# Voltage_Source.net
KiCad netlist of a schematic drawn in Altium Designer
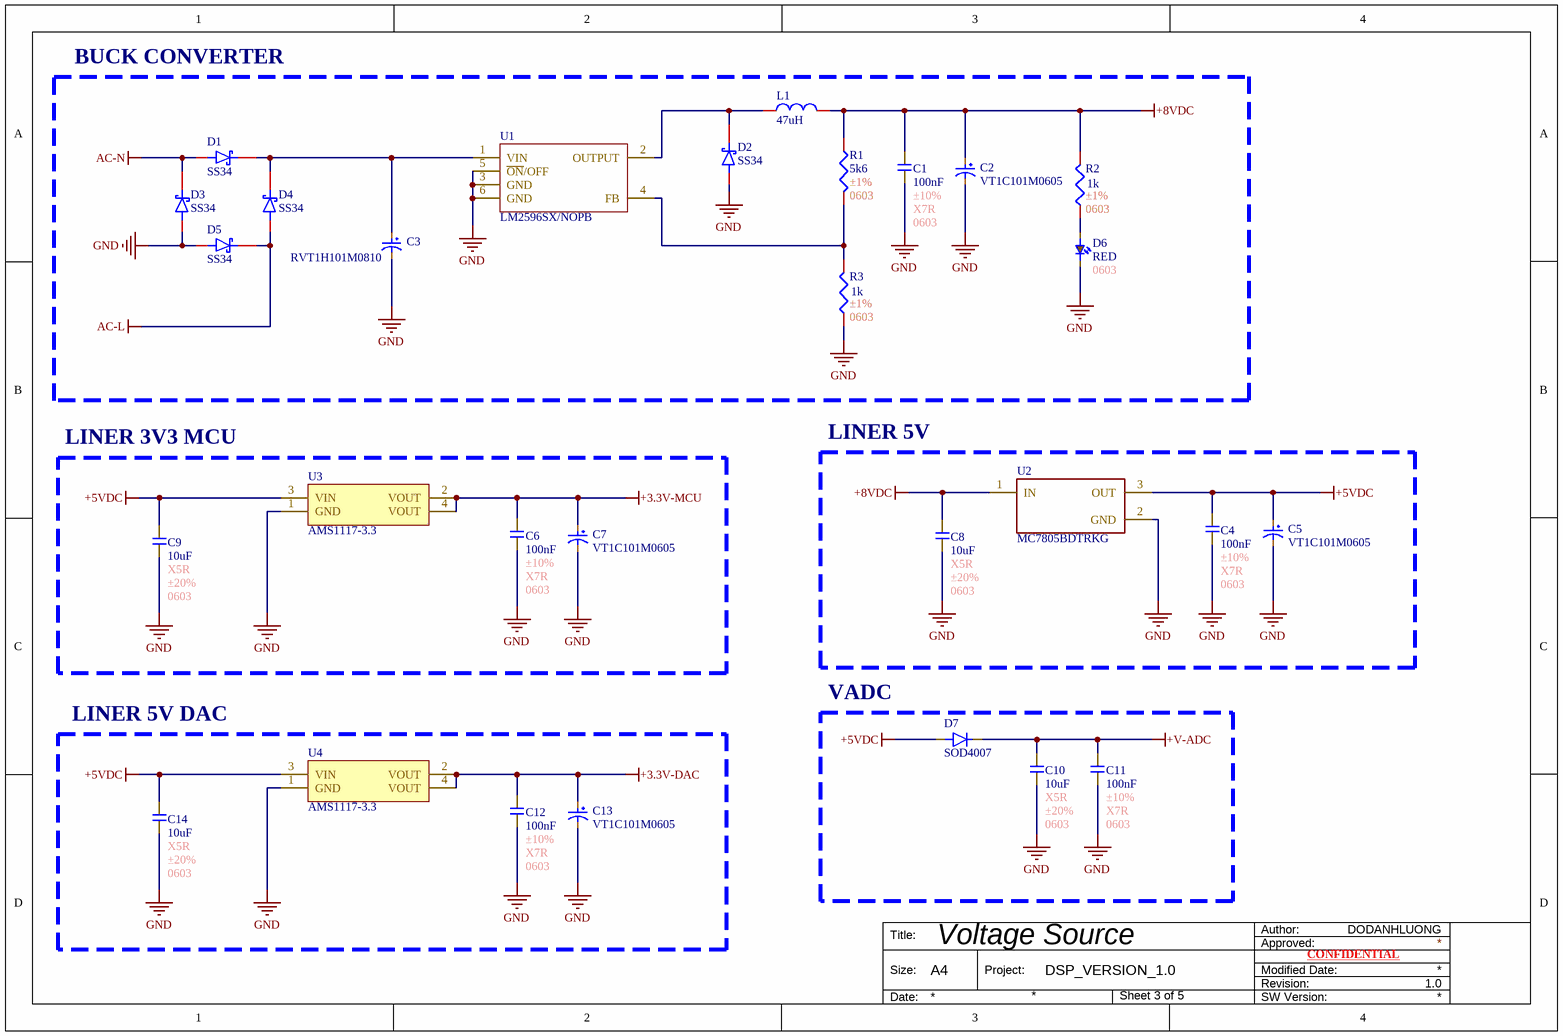
[diagram p0: Voltage Source.SchDoc]

(export (version "E")
  (design (tool "Eeschema 10.0.6"))
  (components
    (comp (ref "C1")
      (value "100nF")
      (footprint "C0603")
      (description "50V 100nF X7R ±10% 0603 Multilayer Ceramic Capacitors MLCC - SMD/SMT ROHS")
      (fields
        (field (name "MANUFACTURER") "YAGEO")
        (field (name "MFR. PART #") "CC0603KRX7R9BB104")
        (field (name "TOLERANCE") "±10%")
        (field (name "TEMPERATURE COEFFICIENT") "X7R")
        (field (name "PACKAGE") "0603")
      )
      (libsource (lib "DSP_VERSION_1.0") (part "C0603_100nF_±10%_X7R"))
    )
    (comp (ref "C2")
      (value "VT1C101M0605")
      (footprint "C_100uF_16V_Aluminum")
      (description "100uF 16V ±20% 63mA@120Hz SMD,D6.3xL5.4mm Aluminum Electrolytic Capacitors RoHS")
      (fields (field (name "MANUFACTURER") "ROQANG") (field (name "LCSC PART #") "C90273"))
      (libsource (lib "Capital") (part "C_100uF_16V_aluminum"))
    )
    (comp (ref "C3")
      (value "RVT1H101M0810")
      (footprint "C_100uF_Aluminum")
      (description "100uF 50V ±20% 146mA@120Hz SMD,D8xL10.2mm Aluminum Electrolytic Capacitors RoHS")
      (fields (field (name "MANUFACTURER") "ROQANG") (field (name "LCSC PART #") "C72480"))
      (libsource (lib "Capital") (part "C_100uF_aluminum"))
    )
    (comp (ref "C4")
      (value "100nF")
      (footprint "C0603")
      (description "50V 100nF X7R ±10% 0603 Multilayer Ceramic Capacitors MLCC - SMD/SMT ROHS")
      (fields
        (field (name "MANUFACTURER") "YAGEO")
        (field (name "MFR. PART #") "CC0603KRX7R9BB104")
        (field (name "TOLERANCE") "±10%")
        (field (name "TEMPERATURE COEFFICIENT") "X7R")
        (field (name "PACKAGE") "0603")
      )
      (libsource (lib "DSP_VERSION_1.0") (part "C0603_100nF_±10%_X7R"))
    )
    (comp (ref "C5")
      (value "VT1C101M0605")
      (footprint "C_100uF_16V_Aluminum")
      (description "100uF 16V ±20% 63mA@120Hz SMD,D6.3xL5.4mm Aluminum Electrolytic Capacitors RoHS")
      (fields (field (name "MANUFACTURER") "ROQANG") (field (name "LCSC PART #") "C90273"))
      (libsource (lib "Capital") (part "C_100uF_16V_aluminum"))
    )
    (comp (ref "C6")
      (value "100nF")
      (footprint "C0603")
      (description "50V 100nF X7R ±10% 0603 Multilayer Ceramic Capacitors MLCC - SMD/SMT ROHS")
      (fields
        (field (name "MANUFACTURER") "YAGEO")
        (field (name "MFR. PART #") "CC0603KRX7R9BB104")
        (field (name "TOLERANCE") "±10%")
        (field (name "TEMPERATURE COEFFICIENT") "X7R")
        (field (name "PACKAGE") "0603")
      )
      (libsource (lib "DSP_VERSION_1.0") (part "C0603_100nF_±10%_X7R"))
    )
    (comp (ref "C7")
      (value "VT1C101M0605")
      (footprint "C_100uF_16V_Aluminum")
      (description "100uF 16V ±20% 63mA@120Hz SMD,D6.3xL5.4mm Aluminum Electrolytic Capacitors RoHS")
      (fields (field (name "MANUFACTURER") "ROQANG") (field (name "LCSC PART #") "C90273"))
      (libsource (lib "Capital") (part "C_100uF_16V_aluminum"))
    )
    (comp (ref "C8")
      (value "10uF")
      (footprint "C0603")
      (description "25V 10uF X5R ±20% 0603 Multilayer Ceramic Capacitors MLCC - SMD/SMT ROHS")
      (fields
        (field (name "MANUFACTURER") "YAGEO")
        (field (name "MFR. PART #") "CC0603MRX5R8BB106")
        (field (name "TEMPERATURE COEFFICIENT") "X5R")
        (field (name "TOLERANCE") "±20%")
        (field (name "PACKAGE") "0603")
      )
      (libsource (lib "DSP_VERSION_1.0") (part "C0603_10uF_±10%_X7R"))
    )
    (comp (ref "C9")
      (value "10uF")
      (footprint "C0603")
      (description "25V 10uF X5R ±20% 0603 Multilayer Ceramic Capacitors MLCC - SMD/SMT ROHS")
      (fields
        (field (name "MANUFACTURER") "YAGEO")
        (field (name "MFR. PART #") "CC0603MRX5R8BB106")
        (field (name "TEMPERATURE COEFFICIENT") "X5R")
        (field (name "TOLERANCE") "±20%")
        (field (name "PACKAGE") "0603")
      )
      (libsource (lib "DSP_VERSION_1.0") (part "C0603_10uF_±10%_X7R"))
    )
    (comp (ref "C10")
      (value "10uF")
      (footprint "C0603")
      (description "25V 10uF X5R ±20% 0603 Multilayer Ceramic Capacitors MLCC - SMD/SMT ROHS")
      (fields
        (field (name "MANUFACTURER") "YAGEO")
        (field (name "MFR. PART #") "CC0603MRX5R8BB106")
        (field (name "TEMPERATURE COEFFICIENT") "X5R")
        (field (name "TOLERANCE") "±20%")
        (field (name "PACKAGE") "0603")
      )
      (libsource (lib "DSP_VERSION_1.0") (part "C0603_10uF_±10%_X7R"))
    )
    (comp (ref "C11")
      (value "100nF")
      (footprint "C0603")
      (description "50V 100nF X7R ±10% 0603 Multilayer Ceramic Capacitors MLCC - SMD/SMT ROHS")
      (fields
        (field (name "MANUFACTURER") "YAGEO")
        (field (name "MFR. PART #") "CC0603KRX7R9BB104")
        (field (name "TOLERANCE") "±10%")
        (field (name "TEMPERATURE COEFFICIENT") "X7R")
        (field (name "PACKAGE") "0603")
      )
      (libsource (lib "DSP_VERSION_1.0") (part "C0603_100nF_±10%_X7R"))
    )
    (comp (ref "C12")
      (value "100nF")
      (footprint "C0603")
      (description "50V 100nF X7R ±10% 0603 Multilayer Ceramic Capacitors MLCC - SMD/SMT ROHS")
      (fields
        (field (name "MANUFACTURER") "YAGEO")
        (field (name "MFR. PART #") "CC0603KRX7R9BB104")
        (field (name "TOLERANCE") "±10%")
        (field (name "TEMPERATURE COEFFICIENT") "X7R")
        (field (name "PACKAGE") "0603")
      )
      (libsource (lib "DSP_VERSION_1.0") (part "C0603_100nF_±10%_X7R"))
    )
    (comp (ref "C13")
      (value "VT1C101M0605")
      (footprint "C_100uF_16V_Aluminum")
      (description "100uF 16V ±20% 63mA@120Hz SMD,D6.3xL5.4mm Aluminum Electrolytic Capacitors RoHS")
      (fields (field (name "MANUFACTURER") "ROQANG") (field (name "LCSC PART #") "C90273"))
      (libsource (lib "Capital") (part "C_100uF_16V_aluminum"))
    )
    (comp (ref "C14")
      (value "10uF")
      (footprint "C0603")
      (description "25V 10uF X5R ±20% 0603 Multilayer Ceramic Capacitors MLCC - SMD/SMT ROHS")
      (fields
        (field (name "MANUFACTURER") "YAGEO")
        (field (name "MFR. PART #") "CC0603MRX5R8BB106")
        (field (name "TEMPERATURE COEFFICIENT") "X5R")
        (field (name "TOLERANCE") "±20%")
        (field (name "PACKAGE") "0603")
      )
      (libsource (lib "DSP_VERSION_1.0") (part "C0603_10uF_±10%_X7R"))
    )
    (comp (ref "D1")
      (value "SS34")
      (footprint "SS34")
      (description "40V Independent 3A 550mV@3A SMA(DO-214AC) Schottky Diodes ROHS")
      (fields
        (field (name "MANUFACTURER") "MDD(Microdiode Semiconductor)")
        (field (name "LCSC PART #") "C8678")
      )
      (libsource (lib "Diode") (part "SS34"))
    )
    (comp (ref "D2")
      (value "SS34")
      (footprint "SS34")
      (description "40V Independent 3A 550mV@3A SMA(DO-214AC) Schottky Diodes ROHS")
      (fields
        (field (name "MANUFACTURER") "MDD(Microdiode Semiconductor)")
        (field (name "LCSC PART #") "C8678")
      )
      (libsource (lib "Diode") (part "SS34"))
    )
    (comp (ref "D3")
      (value "SS34")
      (footprint "SS34")
      (description "40V Independent 3A 550mV@3A SMA(DO-214AC) Schottky Diodes ROHS")
      (fields
        (field (name "MANUFACTURER") "MDD(Microdiode Semiconductor)")
        (field (name "LCSC PART #") "C8678")
      )
      (libsource (lib "Diode") (part "SS34"))
    )
    (comp (ref "D4")
      (value "SS34")
      (footprint "SS34")
      (description "40V Independent 3A 550mV@3A SMA(DO-214AC) Schottky Diodes ROHS")
      (fields
        (field (name "MANUFACTURER") "MDD(Microdiode Semiconductor)")
        (field (name "LCSC PART #") "C8678")
      )
      (libsource (lib "Diode") (part "SS34"))
    )
    (comp (ref "D5")
      (value "SS34")
      (footprint "SS34")
      (description "40V Independent 3A 550mV@3A SMA(DO-214AC) Schottky Diodes ROHS")
      (fields
        (field (name "MANUFACTURER") "MDD(Microdiode Semiconductor)")
        (field (name "LCSC PART #") "C8678")
      )
      (libsource (lib "Diode") (part "SS34"))
    )
    (comp (ref "D6")
      (value "RED")
      (footprint "LED0603")
      (description "25mcd~40mcd Water Clear -40℃~+85℃ 624nm Red 120° 60mW 0402 LED Indication - Discrete ROHS")
      (fields
        (field (name "MANUFACTURER") "XINGLIGHT")
        (field (name "MFR. PART #") "XL-1005UGC")
        (field (name "PACKAGE") "0603")
      )
      (libsource (lib "LED") (part "D0603_RED"))
    )
    (comp (ref "D7")
      (value "SOD4007")
      (footprint "SOD4007")
      (description "1A Independent 1kV 1.1V@1A SOD-123FL Diodes - General Purpose ROHS")
      (fields
        (field (name "MANUFACTURER") "MDD(Microdiode Semiconductor)")
        (field (name "LCSC PART #") "C18124")
      )
      (libsource (lib "Diode") (part "SOD4007"))
    )
    (comp (ref "L1")
      (value "47uH")
      (footprint "CD43")
      (description "1.15A 10uH Unshielded Inductor ±20% SMD,4x4.5mm Power Inductors ROHS")
      (fields (field (name "MANUFACTURER") "ZE") (field (name "MFR. PART #") "CD43-100M"))
      (libsource (lib "Inductor") (part "CD4-10UH"))
    )
    (comp (ref "R1")
      (value "5k6")
      (footprint "R0603")
      (description "62.5mW Thick Film Resistor 50V ±1% ±200ppm/℃ 10Ω 0402 Chip Resistor - Surface Mount ROHS")
      (fields
        (field (name "MANUFACTURER") "YAGEO")
        (field (name "MFR. PART #") "RC0402FR-0710RL")
        (field (name "TOLERANCE") "±1%")
        (field (name "PACKAGE") "0603")
      )
      (libsource (lib "Resistor") (part "R0603_4k7Ω_±1%"))
    )
    (comp (ref "R2")
      (value "1k")
      (footprint "R0603")
      (description "62.5mW Thick Film Resistor 50V ±1% ±200ppm/℃ 10Ω 0402 Chip Resistor - Surface Mount ROHS")
      (fields
        (field (name "MANUFACTURER") "YAGEO")
        (field (name "MFR. PART #") "RC0402FR-0710RL")
        (field (name "TOLERANCE") "±1%")
        (field (name "PACKAGE") "0603")
      )
      (libsource (lib "Resistor") (part "R0603_4k7Ω_±1%"))
    )
    (comp (ref "R3")
      (value "1k")
      (footprint "R0603")
      (description "62.5mW Thick Film Resistor 50V ±1% ±200ppm/℃ 10Ω 0402 Chip Resistor - Surface Mount ROHS")
      (fields
        (field (name "MANUFACTURER") "YAGEO")
        (field (name "MFR. PART #") "RC0402FR-0710RL")
        (field (name "TOLERANCE") "±1%")
        (field (name "PACKAGE") "0603")
      )
      (libsource (lib "Resistor") (part "R0603_4k7Ω_±1%"))
    )
    (comp (ref "U1")
      (value "LM2596SX/NOPB")
      (footprint "LM2596SX-5.0/NOPB")
      (description "150kHz Buck Fixed 1 TO-263-5 Voltage Regulators - DC DC Switching Regulators RoHS")
      (fields (field (name "MANUFACTURER") "TI") (field (name "LCSC PART #") "C10002"))
      (libsource (lib "IC") (part "LM2596SX/NOPB"))
    )
    (comp (ref "U2")
      (value "MC7805BDTRKG")
      (footprint "7805")
      (fields (field (name "MANUFACTURER") "onsemi") (field (name "LCSC PART #") "C110908"))
      (libsource (lib "IC") (part "7805"))
    )
    (comp (ref "U3")
      (value "AMS1117-3.3")
      (footprint "AMS1117-3.3")
      (fields
        (field (name "MANUFACTURER") "Advanced Monolithic Systems")
        (field (name "LCSC PART #") "C6186")
      )
      (libsource (lib "IC") (part "AMS1117-3.3"))
    )
    (comp (ref "U4")
      (value "AMS1117-3.3")
      (footprint "AMS1117-3.3")
      (fields
        (field (name "MANUFACTURER") "Advanced Monolithic Systems")
        (field (name "LCSC PART #") "C6186")
      )
      (libsource (lib "IC") (part "AMS1117-3.3"))
    )
  )
  (nets
    (net (code "1") (name "+3.3V-DAC") (class "Default")
      (node (ref "C12") (pin "2") (pinfunction "2_2") (pintype "passive"))
      (node (ref "C13") (pin "1") (pinfunction "1_1") (pintype "passive"))
      (node (ref "U4") (pin "2") (pinfunction "VOUT_2") (pintype "passive"))
      (node (ref "U4") (pin "4") (pinfunction "VOUT_4") (pintype "passive"))
    )
    (net (code "2") (name "+3.3V-MCU") (class "Default")
      (node (ref "C6") (pin "2") (pinfunction "2_2") (pintype "passive"))
      (node (ref "C7") (pin "1") (pinfunction "1_1") (pintype "passive"))
      (node (ref "U3") (pin "2") (pinfunction "VOUT_2") (pintype "passive"))
      (node (ref "U3") (pin "4") (pinfunction "VOUT_4") (pintype "passive"))
    )
    (net (code "3") (name "+5VDC") (class "Default")
      (node (ref "C14") (pin "2") (pinfunction "2_2") (pintype "passive"))
      (node (ref "C4") (pin "2") (pinfunction "2_2") (pintype "passive"))
      (node (ref "C5") (pin "1") (pinfunction "1_1") (pintype "passive"))
      (node (ref "C9") (pin "2") (pinfunction "2_2") (pintype "passive"))
      (node (ref "D7") (pin "2") (pinfunction "A_2") (pintype "passive"))
      (node (ref "U2") (pin "3") (pinfunction "OUT_3") (pintype "passive"))
      (node (ref "U3") (pin "3") (pinfunction "VIN_3") (pintype "passive"))
      (node (ref "U4") (pin "3") (pinfunction "VIN_3") (pintype "passive"))
    )
    (net (code "4") (name "+8VDC") (class "Default")
      (node (ref "C1") (pin "2") (pinfunction "2_2") (pintype "passive"))
      (node (ref "C2") (pin "1") (pinfunction "1_1") (pintype "passive"))
      (node (ref "C8") (pin "2") (pinfunction "2_2") (pintype "passive"))
      (node (ref "L1") (pin "2") (pinfunction "2_2") (pintype "passive"))
      (node (ref "R1") (pin "1") (pinfunction "1_1") (pintype "passive"))
      (node (ref "R2") (pin "2") (pinfunction "2_2") (pintype "passive"))
      (node (ref "U2") (pin "1") (pinfunction "IN_1") (pintype "passive"))
    )
    (net (code "5") (name "+V-ADC") (class "Default")
      (node (ref "C10") (pin "2") (pinfunction "2_2") (pintype "passive"))
      (node (ref "C11") (pin "2") (pinfunction "2_2") (pintype "passive"))
      (node (ref "D7") (pin "1") (pinfunction "C_1") (pintype "passive"))
    )
    (net (code "6") (name "AC-L") (class "Default")
      (node (ref "D4") (pin "2") (pinfunction "2_2") (pintype "passive"))
      (node (ref "D5") (pin "1") (pinfunction "1_1") (pintype "passive"))
    )
    (net (code "7") (name "AC-N") (class "Default")
      (node (ref "D1") (pin "2") (pinfunction "2_2") (pintype "passive"))
      (node (ref "D3") (pin "1") (pinfunction "1_1") (pintype "passive"))
    )
    (net (code "8") (name "GND") (class "Default")
      (node (ref "C1") (pin "1") (pinfunction "1_1") (pintype "passive"))
      (node (ref "C10") (pin "1") (pinfunction "1_1") (pintype "passive"))
      (node (ref "C11") (pin "1") (pinfunction "1_1") (pintype "passive"))
      (node (ref "C12") (pin "1") (pinfunction "1_1") (pintype "passive"))
      (node (ref "C13") (pin "2") (pinfunction "2_2") (pintype "passive"))
      (node (ref "C14") (pin "1") (pinfunction "1_1") (pintype "passive"))
      (node (ref "C2") (pin "2") (pinfunction "2_2") (pintype "passive"))
      (node (ref "C3") (pin "2") (pinfunction "2_2") (pintype "passive"))
      (node (ref "C4") (pin "1") (pinfunction "1_1") (pintype "passive"))
      (node (ref "C5") (pin "2") (pinfunction "2_2") (pintype "passive"))
      (node (ref "C6") (pin "1") (pinfunction "1_1") (pintype "passive"))
      (node (ref "C7") (pin "2") (pinfunction "2_2") (pintype "passive"))
      (node (ref "C8") (pin "1") (pinfunction "1_1") (pintype "passive"))
      (node (ref "C9") (pin "1") (pinfunction "1_1") (pintype "passive"))
      (node (ref "D2") (pin "2") (pinfunction "2_2") (pintype "passive"))
      (node (ref "D3") (pin "2") (pinfunction "2_2") (pintype "passive"))
      (node (ref "D5") (pin "2") (pinfunction "2_2") (pintype "passive"))
      (node (ref "D6") (pin "1") (pinfunction "1_1") (pintype "passive"))
      (node (ref "R3") (pin "1") (pinfunction "1_1") (pintype "passive"))
      (node (ref "U1") (pin "3") (pinfunction "GND_3") (pintype "passive"))
      (node (ref "U1") (pin "5") (pinfunction "~{ON}/OFF_5") (pintype "passive"))
      (node (ref "U1") (pin "6") (pinfunction "GND_6") (pintype "passive"))
      (node (ref "U2") (pin "2") (pinfunction "GND_2") (pintype "power_in"))
      (node (ref "U3") (pin "1") (pinfunction "GND_1") (pintype "passive"))
      (node (ref "U4") (pin "1") (pinfunction "GND_1") (pintype "passive"))
    )
    (net (code "9") (name "Net-(D6-Pad2)") (class "Default")
      (node (ref "D6") (pin "2") (pinfunction "2_2") (pintype "passive"))
      (node (ref "R2") (pin "1") (pinfunction "1_1") (pintype "passive"))
    )
    (net (code "10") (name "Net-(U1-FB)") (class "Default")
      (node (ref "R1") (pin "2") (pinfunction "2_2") (pintype "passive"))
      (node (ref "R3") (pin "2") (pinfunction "2_2") (pintype "passive"))
      (node (ref "U1") (pin "4") (pinfunction "FB_4") (pintype "passive"))
    )
    (net (code "11") (name "Net-(U1-OUTPUT)") (class "Default")
      (node (ref "D2") (pin "1") (pinfunction "1_1") (pintype "passive"))
      (node (ref "L1") (pin "1") (pinfunction "1_1") (pintype "passive"))
      (node (ref "U1") (pin "2") (pinfunction "OUTPUT_2") (pintype "passive"))
    )
    (net (code "12") (name "Net-(U1-VIN)") (class "Default")
      (node (ref "C3") (pin "1") (pinfunction "1_1") (pintype "passive"))
      (node (ref "D1") (pin "1") (pinfunction "1_1") (pintype "passive"))
      (node (ref "D4") (pin "1") (pinfunction "1_1") (pintype "passive"))
      (node (ref "U1") (pin "1") (pinfunction "VIN_1") (pintype "passive"))
    )
  )
)
